# IS31SE5117-Breakout.net
KiCad netlist of a schematic drawn in EAGLE
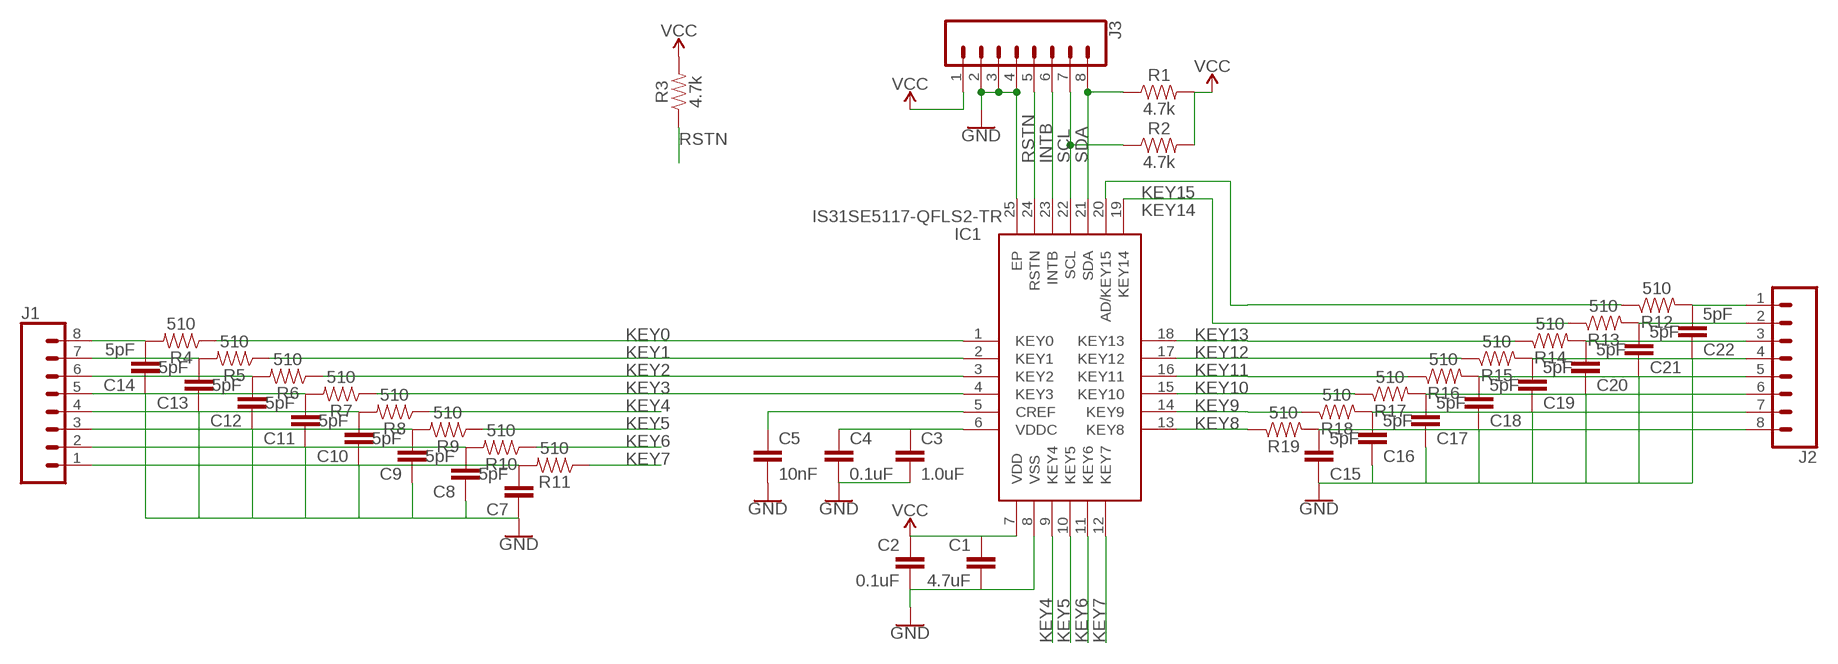
[diagram p0: schematic, sheet 1]

(export (version "E")
  (design (tool "Eeschema 10.0.6"))
  (components
    (comp (ref "C1")
      (value "4.7uF")
      (footprint "eagle-import:0603")
      (libsource (lib "eagle-import") (part "1.0UF-0603-16V-10%-X7R"))
    )
    (comp (ref "C2")
      (value "0.1uF")
      (footprint "eagle-import:0603")
      (libsource (lib "eagle-import") (part "0.1UF-0603-25V-10%-X7R-WE"))
    )
    (comp (ref "C3")
      (value "1.0uF")
      (footprint "eagle-import:0603")
      (libsource (lib "eagle-import") (part "1.0UF-0603-16V-10%-X7R"))
    )
    (comp (ref "C4")
      (value "0.1uF")
      (footprint "eagle-import:0603")
      (libsource (lib "eagle-import") (part "0.1UF-0603-25V-10%-X7R-WE"))
    )
    (comp (ref "C5")
      (value "10nF")
      (footprint "eagle-import:0603")
      (libsource (lib "eagle-import") (part "10NF-0603-50V-10%"))
    )
    (comp (ref "C7")
      (value "5pF")
      (footprint "eagle-import:0603")
      (libsource (lib "eagle-import") (part "10NF-0603-50V-10%"))
    )
    (comp (ref "C8")
      (value "5pF")
      (footprint "eagle-import:0603")
      (libsource (lib "eagle-import") (part "10NF-0603-50V-10%"))
    )
    (comp (ref "C9")
      (value "5pF")
      (footprint "eagle-import:0603")
      (libsource (lib "eagle-import") (part "10NF-0603-50V-10%"))
    )
    (comp (ref "C10")
      (value "5pF")
      (footprint "eagle-import:0603")
      (libsource (lib "eagle-import") (part "10NF-0603-50V-10%"))
    )
    (comp (ref "C11")
      (value "5pF")
      (footprint "eagle-import:0603")
      (libsource (lib "eagle-import") (part "10NF-0603-50V-10%"))
    )
    (comp (ref "C12")
      (value "5pF")
      (footprint "eagle-import:0603")
      (libsource (lib "eagle-import") (part "10NF-0603-50V-10%"))
    )
    (comp (ref "C13")
      (value "5pF")
      (footprint "eagle-import:0603")
      (libsource (lib "eagle-import") (part "10NF-0603-50V-10%"))
    )
    (comp (ref "C14")
      (value "5pF")
      (footprint "eagle-import:0603")
      (libsource (lib "eagle-import") (part "10NF-0603-50V-10%"))
    )
    (comp (ref "C15")
      (value "5pF")
      (footprint "eagle-import:0603")
      (libsource (lib "eagle-import") (part "10NF-0603-50V-10%"))
    )
    (comp (ref "C16")
      (value "5pF")
      (footprint "eagle-import:0603")
      (libsource (lib "eagle-import") (part "10NF-0603-50V-10%"))
    )
    (comp (ref "C17")
      (value "5pF")
      (footprint "eagle-import:0603")
      (libsource (lib "eagle-import") (part "10NF-0603-50V-10%"))
    )
    (comp (ref "C18")
      (value "5pF")
      (footprint "eagle-import:0603")
      (libsource (lib "eagle-import") (part "10NF-0603-50V-10%"))
    )
    (comp (ref "C19")
      (value "5pF")
      (footprint "eagle-import:0603")
      (libsource (lib "eagle-import") (part "10NF-0603-50V-10%"))
    )
    (comp (ref "C20")
      (value "5pF")
      (footprint "eagle-import:0603")
      (libsource (lib "eagle-import") (part "10NF-0603-50V-10%"))
    )
    (comp (ref "C21")
      (value "5pF")
      (footprint "eagle-import:0603")
      (libsource (lib "eagle-import") (part "10NF-0603-50V-10%"))
    )
    (comp (ref "C22")
      (value "5pF")
      (footprint "eagle-import:0603")
      (libsource (lib "eagle-import") (part "10NF-0603-50V-10%"))
    )
    (comp (ref "IC1")
      (value "IS31SE5117-QFLS2-TR")
      (footprint "eagle-import:QFN50P400X400X65-25N")
      (fields (field (name "MOUSER_PART_NUMBER") "870-IS31SE517QFLS2TR"))
      (libsource (lib "eagle-import") (part "IS31SE5117-QFLS2-TR"))
    )
    (comp (ref "J1")
      (value "CONN_08LONGPADS")
      (footprint "eagle-import:1X08_LONGPADS")
      (libsource (lib "eagle-import") (part "CONN_08LONGPADS"))
    )
    (comp (ref "J2")
      (value "CONN_08LONGPADS")
      (footprint "eagle-import:1X08_LONGPADS")
      (libsource (lib "eagle-import") (part "CONN_08LONGPADS"))
    )
    (comp (ref "J3")
      (value "CONN_08LONGPADS")
      (footprint "eagle-import:1X08_LONGPADS")
      (libsource (lib "eagle-import") (part "CONN_08LONGPADS"))
    )
    (comp (ref "R1")
      (value "4.7k")
      (footprint "eagle-import:0603")
      (libsource (lib "eagle-import") (part "4.7KOHM-0603-1/10W-1%"))
    )
    (comp (ref "R2")
      (value "4.7k")
      (footprint "eagle-import:0603")
      (libsource (lib "eagle-import") (part "4.7KOHM-0603-1/10W-1%"))
    )
    (comp (ref "R3")
      (value "4.7k")
      (footprint "eagle-import:0603")
      (libsource (lib "eagle-import") (part "4.7KOHM-0603-1/10W-1%"))
    )
    (comp (ref "R4")
      (value "510")
      (footprint "eagle-import:0603")
      (libsource (lib "eagle-import") (part "4.7KOHM-0603-1/10W-1%"))
    )
    (comp (ref "R5")
      (value "510")
      (footprint "eagle-import:0603")
      (libsource (lib "eagle-import") (part "4.7KOHM-0603-1/10W-1%"))
    )
    (comp (ref "R6")
      (value "510")
      (footprint "eagle-import:0603")
      (libsource (lib "eagle-import") (part "4.7KOHM-0603-1/10W-1%"))
    )
    (comp (ref "R7")
      (value "510")
      (footprint "eagle-import:0603")
      (libsource (lib "eagle-import") (part "4.7KOHM-0603-1/10W-1%"))
    )
    (comp (ref "R8")
      (value "510")
      (footprint "eagle-import:0603")
      (libsource (lib "eagle-import") (part "4.7KOHM-0603-1/10W-1%"))
    )
    (comp (ref "R9")
      (value "510")
      (footprint "eagle-import:0603")
      (libsource (lib "eagle-import") (part "4.7KOHM-0603-1/10W-1%"))
    )
    (comp (ref "R10")
      (value "510")
      (footprint "eagle-import:0603")
      (libsource (lib "eagle-import") (part "4.7KOHM-0603-1/10W-1%"))
    )
    (comp (ref "R11")
      (value "510")
      (footprint "eagle-import:0603")
      (libsource (lib "eagle-import") (part "4.7KOHM-0603-1/10W-1%"))
    )
    (comp (ref "R12")
      (value "510")
      (footprint "eagle-import:0603")
      (libsource (lib "eagle-import") (part "4.7KOHM-0603-1/10W-1%"))
    )
    (comp (ref "R13")
      (value "510")
      (footprint "eagle-import:0603")
      (libsource (lib "eagle-import") (part "4.7KOHM-0603-1/10W-1%"))
    )
    (comp (ref "R14")
      (value "510")
      (footprint "eagle-import:0603")
      (libsource (lib "eagle-import") (part "4.7KOHM-0603-1/10W-1%"))
    )
    (comp (ref "R15")
      (value "510")
      (footprint "eagle-import:0603")
      (libsource (lib "eagle-import") (part "4.7KOHM-0603-1/10W-1%"))
    )
    (comp (ref "R16")
      (value "510")
      (footprint "eagle-import:0603")
      (libsource (lib "eagle-import") (part "4.7KOHM-0603-1/10W-1%"))
    )
    (comp (ref "R17")
      (value "510")
      (footprint "eagle-import:0603")
      (libsource (lib "eagle-import") (part "4.7KOHM-0603-1/10W-1%"))
    )
    (comp (ref "R18")
      (value "510")
      (footprint "eagle-import:0603")
      (libsource (lib "eagle-import") (part "4.7KOHM-0603-1/10W-1%"))
    )
    (comp (ref "R19")
      (value "510")
      (footprint "eagle-import:0603")
      (libsource (lib "eagle-import") (part "4.7KOHM-0603-1/10W-1%"))
    )
  )
  (nets
    (net (code "1") (name "/INTB") (class "Default")
      (node (ref "IC1") (pin "23") (pinfunction "INTB_23") (pintype "bidirectional"))
      (node (ref "J3") (pin "6") (pinfunction "6_6") (pintype "passive"))
    )
    (net (code "2") (name "/KEY0") (class "Default")
      (node (ref "IC1") (pin "1") (pinfunction "KEY0_1") (pintype "bidirectional"))
      (node (ref "R4") (pin "1") (pinfunction "1_1") (pintype "passive"))
    )
    (net (code "3") (name "/KEY1") (class "Default")
      (node (ref "IC1") (pin "2") (pinfunction "KEY1_2") (pintype "bidirectional"))
      (node (ref "R5") (pin "1") (pinfunction "1_1") (pintype "passive"))
    )
    (net (code "4") (name "/KEY2") (class "Default")
      (node (ref "IC1") (pin "3") (pinfunction "KEY2_3") (pintype "bidirectional"))
      (node (ref "R6") (pin "1") (pinfunction "1_1") (pintype "passive"))
    )
    (net (code "5") (name "/KEY3") (class "Default")
      (node (ref "IC1") (pin "4") (pinfunction "KEY3_4") (pintype "bidirectional"))
      (node (ref "R7") (pin "1") (pinfunction "1_1") (pintype "passive"))
    )
    (net (code "6") (name "/KEY4") (class "Default")
      (node (ref "IC1") (pin "9") (pinfunction "KEY4_9") (pintype "bidirectional"))
      (node (ref "R8") (pin "1") (pinfunction "1_1") (pintype "passive"))
    )
    (net (code "7") (name "/KEY5") (class "Default")
      (node (ref "IC1") (pin "10") (pinfunction "KEY5_10") (pintype "bidirectional"))
      (node (ref "R9") (pin "1") (pinfunction "1_1") (pintype "passive"))
    )
    (net (code "8") (name "/KEY6") (class "Default")
      (node (ref "IC1") (pin "11") (pinfunction "KEY6_11") (pintype "bidirectional"))
      (node (ref "R10") (pin "1") (pinfunction "1_1") (pintype "passive"))
    )
    (net (code "9") (name "/KEY7") (class "Default")
      (node (ref "IC1") (pin "12") (pinfunction "KEY7_12") (pintype "bidirectional"))
      (node (ref "R11") (pin "1") (pinfunction "1_1") (pintype "passive"))
    )
    (net (code "10") (name "/KEY8") (class "Default")
      (node (ref "IC1") (pin "13") (pinfunction "KEY8_13") (pintype "bidirectional"))
      (node (ref "R19") (pin "1") (pinfunction "1_1") (pintype "passive"))
    )
    (net (code "11") (name "/KEY9") (class "Default")
      (node (ref "IC1") (pin "14") (pinfunction "KEY9_14") (pintype "bidirectional"))
      (node (ref "R18") (pin "1") (pinfunction "1_1") (pintype "passive"))
    )
    (net (code "12") (name "/KEY10") (class "Default")
      (node (ref "IC1") (pin "15") (pinfunction "KEY10_15") (pintype "bidirectional"))
      (node (ref "R17") (pin "1") (pinfunction "1_1") (pintype "passive"))
    )
    (net (code "13") (name "/KEY11") (class "Default")
      (node (ref "IC1") (pin "16") (pinfunction "KEY11_16") (pintype "bidirectional"))
      (node (ref "R16") (pin "1") (pinfunction "1_1") (pintype "passive"))
    )
    (net (code "14") (name "/KEY12") (class "Default")
      (node (ref "IC1") (pin "17") (pinfunction "KEY12_17") (pintype "bidirectional"))
      (node (ref "R15") (pin "1") (pinfunction "1_1") (pintype "passive"))
    )
    (net (code "15") (name "/KEY13") (class "Default")
      (node (ref "IC1") (pin "18") (pinfunction "KEY13_18") (pintype "bidirectional"))
      (node (ref "R14") (pin "1") (pinfunction "1_1") (pintype "passive"))
    )
    (net (code "16") (name "/KEY14") (class "Default")
      (node (ref "IC1") (pin "19") (pinfunction "KEY14_19") (pintype "bidirectional"))
      (node (ref "R13") (pin "1") (pinfunction "1_1") (pintype "passive"))
    )
    (net (code "17") (name "/KEY15") (class "Default")
      (node (ref "IC1") (pin "20") (pinfunction "AD/KEY15_20") (pintype "bidirectional"))
      (node (ref "R12") (pin "1") (pinfunction "1_1") (pintype "passive"))
    )
    (net (code "18") (name "/RSTN") (class "Default")
      (node (ref "IC1") (pin "24") (pinfunction "RSTN_24") (pintype "bidirectional"))
      (node (ref "J3") (pin "5") (pinfunction "5_5") (pintype "passive"))
      (node (ref "R3") (pin "1") (pinfunction "1_1") (pintype "passive"))
    )
    (net (code "19") (name "/SCL") (class "Default")
      (node (ref "IC1") (pin "22") (pinfunction "SCL_22") (pintype "bidirectional"))
      (node (ref "J3") (pin "7") (pinfunction "7_7") (pintype "passive"))
      (node (ref "R2") (pin "1") (pinfunction "1_1") (pintype "passive"))
    )
    (net (code "20") (name "/SDA") (class "Default")
      (node (ref "IC1") (pin "21") (pinfunction "SDA_21") (pintype "bidirectional"))
      (node (ref "J3") (pin "8") (pinfunction "8_8") (pintype "passive"))
      (node (ref "R1") (pin "1") (pinfunction "1_1") (pintype "passive"))
    )
    (net (code "21") (name "GND") (class "Default")
      (node (ref "C1") (pin "2") (pinfunction "2_2") (pintype "passive"))
      (node (ref "C10") (pin "1") (pinfunction "1_1") (pintype "passive"))
      (node (ref "C11") (pin "1") (pinfunction "1_1") (pintype "passive"))
      (node (ref "C12") (pin "1") (pinfunction "1_1") (pintype "passive"))
      (node (ref "C13") (pin "1") (pinfunction "1_1") (pintype "passive"))
      (node (ref "C14") (pin "1") (pinfunction "1_1") (pintype "passive"))
      (node (ref "C15") (pin "1") (pinfunction "1_1") (pintype "passive"))
      (node (ref "C16") (pin "1") (pinfunction "1_1") (pintype "passive"))
      (node (ref "C17") (pin "1") (pinfunction "1_1") (pintype "passive"))
      (node (ref "C18") (pin "1") (pinfunction "1_1") (pintype "passive"))
      (node (ref "C19") (pin "1") (pinfunction "1_1") (pintype "passive"))
      (node (ref "C2") (pin "2") (pinfunction "2_2") (pintype "passive"))
      (node (ref "C20") (pin "1") (pinfunction "1_1") (pintype "passive"))
      (node (ref "C21") (pin "1") (pinfunction "1_1") (pintype "passive"))
      (node (ref "C22") (pin "1") (pinfunction "1_1") (pintype "passive"))
      (node (ref "C3") (pin "2") (pinfunction "2_2") (pintype "passive"))
      (node (ref "C4") (pin "2") (pinfunction "2_2") (pintype "passive"))
      (node (ref "C5") (pin "2") (pinfunction "2_2") (pintype "passive"))
      (node (ref "C7") (pin "1") (pinfunction "1_1") (pintype "passive"))
      (node (ref "C8") (pin "1") (pinfunction "1_1") (pintype "passive"))
      (node (ref "C9") (pin "1") (pinfunction "1_1") (pintype "passive"))
      (node (ref "IC1") (pin "25") (pinfunction "EP_25") (pintype "bidirectional"))
      (node (ref "IC1") (pin "8") (pinfunction "VSS_8") (pintype "bidirectional"))
      (node (ref "J3") (pin "2") (pinfunction "2_2") (pintype "passive"))
      (node (ref "J3") (pin "3") (pinfunction "3_3") (pintype "passive"))
      (node (ref "J3") (pin "4") (pinfunction "4_4") (pintype "passive"))
    )
    (net (code "22") (name "Net-(C7-Pad2)") (class "Default")
      (node (ref "C7") (pin "2") (pinfunction "2_2") (pintype "passive"))
      (node (ref "J1") (pin "1") (pinfunction "1_1") (pintype "passive"))
      (node (ref "R11") (pin "2") (pinfunction "2_2") (pintype "passive"))
    )
    (net (code "23") (name "Net-(C8-Pad2)") (class "Default")
      (node (ref "C8") (pin "2") (pinfunction "2_2") (pintype "passive"))
      (node (ref "J1") (pin "2") (pinfunction "2_2") (pintype "passive"))
      (node (ref "R10") (pin "2") (pinfunction "2_2") (pintype "passive"))
    )
    (net (code "24") (name "Net-(C9-Pad2)") (class "Default")
      (node (ref "C9") (pin "2") (pinfunction "2_2") (pintype "passive"))
      (node (ref "J1") (pin "3") (pinfunction "3_3") (pintype "passive"))
      (node (ref "R9") (pin "2") (pinfunction "2_2") (pintype "passive"))
    )
    (net (code "25") (name "Net-(C10-Pad2)") (class "Default")
      (node (ref "C10") (pin "2") (pinfunction "2_2") (pintype "passive"))
      (node (ref "J1") (pin "4") (pinfunction "4_4") (pintype "passive"))
      (node (ref "R8") (pin "2") (pinfunction "2_2") (pintype "passive"))
    )
    (net (code "26") (name "Net-(C11-Pad2)") (class "Default")
      (node (ref "C11") (pin "2") (pinfunction "2_2") (pintype "passive"))
      (node (ref "J1") (pin "5") (pinfunction "5_5") (pintype "passive"))
      (node (ref "R7") (pin "2") (pinfunction "2_2") (pintype "passive"))
    )
    (net (code "27") (name "Net-(C12-Pad2)") (class "Default")
      (node (ref "C12") (pin "2") (pinfunction "2_2") (pintype "passive"))
      (node (ref "J1") (pin "6") (pinfunction "6_6") (pintype "passive"))
      (node (ref "R6") (pin "2") (pinfunction "2_2") (pintype "passive"))
    )
    (net (code "28") (name "Net-(C13-Pad2)") (class "Default")
      (node (ref "C13") (pin "2") (pinfunction "2_2") (pintype "passive"))
      (node (ref "J1") (pin "7") (pinfunction "7_7") (pintype "passive"))
      (node (ref "R5") (pin "2") (pinfunction "2_2") (pintype "passive"))
    )
    (net (code "29") (name "Net-(C14-Pad2)") (class "Default")
      (node (ref "C14") (pin "2") (pinfunction "2_2") (pintype "passive"))
      (node (ref "J1") (pin "8") (pinfunction "8_8") (pintype "passive"))
      (node (ref "R4") (pin "2") (pinfunction "2_2") (pintype "passive"))
    )
    (net (code "30") (name "Net-(C15-Pad2)") (class "Default")
      (node (ref "C15") (pin "2") (pinfunction "2_2") (pintype "passive"))
      (node (ref "J2") (pin "8") (pinfunction "8_8") (pintype "passive"))
      (node (ref "R19") (pin "2") (pinfunction "2_2") (pintype "passive"))
    )
    (net (code "31") (name "Net-(C16-Pad2)") (class "Default")
      (node (ref "C16") (pin "2") (pinfunction "2_2") (pintype "passive"))
      (node (ref "J2") (pin "7") (pinfunction "7_7") (pintype "passive"))
      (node (ref "R18") (pin "2") (pinfunction "2_2") (pintype "passive"))
    )
    (net (code "32") (name "Net-(C17-Pad2)") (class "Default")
      (node (ref "C17") (pin "2") (pinfunction "2_2") (pintype "passive"))
      (node (ref "J2") (pin "6") (pinfunction "6_6") (pintype "passive"))
      (node (ref "R17") (pin "2") (pinfunction "2_2") (pintype "passive"))
    )
    (net (code "33") (name "Net-(C18-Pad2)") (class "Default")
      (node (ref "C18") (pin "2") (pinfunction "2_2") (pintype "passive"))
      (node (ref "J2") (pin "5") (pinfunction "5_5") (pintype "passive"))
      (node (ref "R16") (pin "2") (pinfunction "2_2") (pintype "passive"))
    )
    (net (code "34") (name "Net-(C19-Pad2)") (class "Default")
      (node (ref "C19") (pin "2") (pinfunction "2_2") (pintype "passive"))
      (node (ref "J2") (pin "4") (pinfunction "4_4") (pintype "passive"))
      (node (ref "R15") (pin "2") (pinfunction "2_2") (pintype "passive"))
    )
    (net (code "35") (name "Net-(C20-Pad2)") (class "Default")
      (node (ref "C20") (pin "2") (pinfunction "2_2") (pintype "passive"))
      (node (ref "J2") (pin "3") (pinfunction "3_3") (pintype "passive"))
      (node (ref "R14") (pin "2") (pinfunction "2_2") (pintype "passive"))
    )
    (net (code "36") (name "Net-(C21-Pad2)") (class "Default")
      (node (ref "C21") (pin "2") (pinfunction "2_2") (pintype "passive"))
      (node (ref "J2") (pin "2") (pinfunction "2_2") (pintype "passive"))
      (node (ref "R13") (pin "2") (pinfunction "2_2") (pintype "passive"))
    )
    (net (code "37") (name "Net-(C22-Pad2)") (class "Default")
      (node (ref "C22") (pin "2") (pinfunction "2_2") (pintype "passive"))
      (node (ref "J2") (pin "1") (pinfunction "1_1") (pintype "passive"))
      (node (ref "R12") (pin "2") (pinfunction "2_2") (pintype "passive"))
    )
    (net (code "38") (name "Net-(IC1-CREF)") (class "Default")
      (node (ref "C5") (pin "1") (pinfunction "1_1") (pintype "passive"))
      (node (ref "IC1") (pin "5") (pinfunction "CREF_5") (pintype "bidirectional"))
    )
    (net (code "39") (name "Net-(IC1-VDDC)") (class "Default")
      (node (ref "C3") (pin "1") (pinfunction "1_1") (pintype "passive"))
      (node (ref "C4") (pin "1") (pinfunction "1_1") (pintype "passive"))
      (node (ref "IC1") (pin "6") (pinfunction "VDDC_6") (pintype "bidirectional"))
    )
    (net (code "40") (name "VCC") (class "Default")
      (node (ref "C1") (pin "1") (pinfunction "1_1") (pintype "passive"))
      (node (ref "C2") (pin "1") (pinfunction "1_1") (pintype "passive"))
      (node (ref "IC1") (pin "7") (pinfunction "VDD_7") (pintype "bidirectional"))
      (node (ref "J3") (pin "1") (pinfunction "1_1") (pintype "passive"))
      (node (ref "R1") (pin "2") (pinfunction "2_2") (pintype "passive"))
      (node (ref "R2") (pin "2") (pinfunction "2_2") (pintype "passive"))
      (node (ref "R3") (pin "2") (pinfunction "2_2") (pintype "passive"))
    )
  )
)
